# Key_Pass.net
KiCad netlist of a schematic drawn in EAGLE
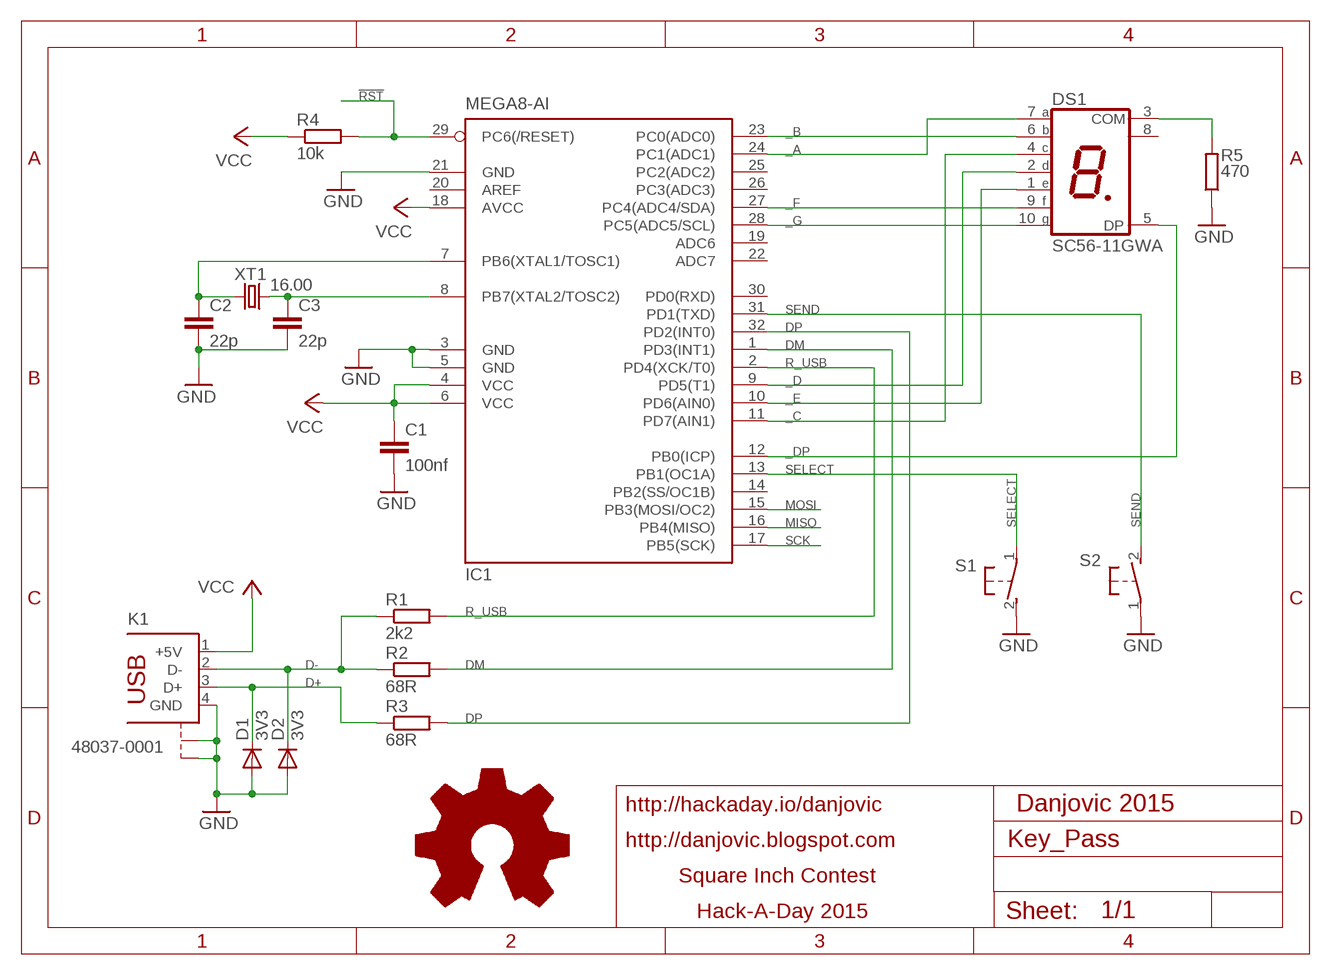
[diagram p0: schematic, sheet 1]

(export (version "E")
  (design (tool "Eeschema 10.0.6"))
  (components
    (comp (ref "C1")
      (value "100nf")
      (footprint "eagle-import:C1206")
      (libsource (lib "eagle-import") (part "C-EUC1206"))
    )
    (comp (ref "C2")
      (value "22p")
      (footprint "eagle-import:C0805")
      (libsource (lib "eagle-import") (part "C-EUC0805"))
    )
    (comp (ref "C3")
      (value "22p")
      (footprint "eagle-import:C0805")
      (libsource (lib "eagle-import") (part "C-EUC0805"))
    )
    (comp (ref "D1")
      (value "3V3")
      (footprint "eagle-import:SOD80C")
      (libsource (lib "eagle-import") (part "DIODE-SOD80C"))
    )
    (comp (ref "D2")
      (value "3V3")
      (footprint "eagle-import:SOD80C")
      (libsource (lib "eagle-import") (part "DIODE-SOD80C"))
    )
    (comp (ref "DS1")
      (value "SC56-11GWA")
      (footprint "eagle-import:SA52-11")
      (libsource (lib "eagle-import") (part "7-SEG_SA52-11"))
    )
    (comp (ref "IC1")
      (value "MEGA8-AI")
      (footprint "eagle-import:TQFP32-08")
      (fields (field (name "MPN") "ATMEGA8-16AU"))
      (libsource (lib "eagle-import") (part "MEGA8-AI"))
    )
    (comp (ref "K1")
      (value "48037-0001")
      (footprint "eagle-import:48037-0001")
      (libsource (lib "eagle-import") (part "48037-0001"))
    )
    (comp (ref "R1")
      (value "2k2")
      (footprint "eagle-import:R0805")
      (libsource (lib "eagle-import") (part "R-EU_R0805"))
    )
    (comp (ref "R2")
      (value "68R")
      (footprint "eagle-import:R0805")
      (libsource (lib "eagle-import") (part "R-EU_R0805"))
    )
    (comp (ref "R3")
      (value "68R")
      (footprint "eagle-import:R0805")
      (libsource (lib "eagle-import") (part "R-EU_R0805"))
    )
    (comp (ref "R4")
      (value "10k")
      (footprint "eagle-import:R0805")
      (libsource (lib "eagle-import") (part "R-EU_R0805"))
    )
    (comp (ref "R5")
      (value "470")
      (footprint "eagle-import:R0805")
      (libsource (lib "eagle-import") (part "R-EU_R0805"))
    )
    (comp (ref "S1")
      (value "31-XX")
      (footprint "eagle-import:B3F-31XX")
      (fields (field (name "MPN") "B3F-3100"))
      (libsource (lib "eagle-import") (part "31-XX"))
    )
    (comp (ref "S2")
      (value "31-XX")
      (footprint "eagle-import:B3F-31XX")
      (fields (field (name "MPN") "B3F-3100"))
      (libsource (lib "eagle-import") (part "31-XX"))
    )
    (comp (ref "XT1")
      (value "16.00")
      (footprint "eagle-import:HC49UP")
      (libsource (lib "eagle-import") (part "CRYSTALHC49UP"))
    )
  )
  (nets
    (net (code "1") (name "/D+") (class "Default")
      (node (ref "D1") (pin "C") (pinfunction "C_C") (pintype "passive"))
      (node (ref "K1") (pin "3") (pinfunction "D+_3") (pintype "passive"))
      (node (ref "R3") (pin "1") (pinfunction "1_1") (pintype "passive"))
    )
    (net (code "2") (name "/D-") (class "Default")
      (node (ref "D2") (pin "C") (pinfunction "C_C") (pintype "passive"))
      (node (ref "K1") (pin "2") (pinfunction "D-_2") (pintype "passive"))
      (node (ref "R1") (pin "1") (pinfunction "1_1") (pintype "passive"))
      (node (ref "R2") (pin "1") (pinfunction "1_1") (pintype "passive"))
    )
    (net (code "3") (name "/DM") (class "Default")
      (node (ref "IC1") (pin "1") (pinfunction "PD3(INT1)_1") (pintype "bidirectional"))
      (node (ref "R2") (pin "2") (pinfunction "2_2") (pintype "passive"))
    )
    (net (code "4") (name "/DP") (class "Default")
      (node (ref "IC1") (pin "32") (pinfunction "PD2(INT0)_32") (pintype "bidirectional"))
      (node (ref "R3") (pin "2") (pinfunction "2_2") (pintype "passive"))
    )
    (net (code "5") (name "/MISO") (class "Default")
      (node (ref "IC1") (pin "16") (pinfunction "PB4(MISO)_16") (pintype "bidirectional"))
    )
    (net (code "6") (name "/MOSI") (class "Default")
      (node (ref "IC1") (pin "15") (pinfunction "PB3(MOSI/OC2)_15") (pintype "bidirectional"))
    )
    (net (code "7") (name "/R_USB") (class "Default")
      (node (ref "IC1") (pin "2") (pinfunction "PD4(XCK/T0)_2") (pintype "bidirectional"))
      (node (ref "R1") (pin "2") (pinfunction "2_2") (pintype "passive"))
    )
    (net (code "8") (name "/SCK") (class "Default")
      (node (ref "IC1") (pin "17") (pinfunction "PB5(SCK)_17") (pintype "bidirectional"))
    )
    (net (code "9") (name "/SELECT") (class "Default")
      (node (ref "IC1") (pin "13") (pinfunction "PB1(OC1A)_13") (pintype "bidirectional"))
      (node (ref "S1") (pin "1") (pinfunction "P_1") (pintype "passive"))
    )
    (net (code "10") (name "/SEND") (class "Default")
      (node (ref "IC1") (pin "31") (pinfunction "PD1(TXD)_31") (pintype "bidirectional"))
      (node (ref "S2") (pin "2") (pinfunction "S_2") (pintype "passive"))
    )
    (net (code "11") (name "/_A") (class "Default")
      (node (ref "DS1") (pin "7") (pinfunction "A_7") (pintype "passive"))
      (node (ref "IC1") (pin "24") (pinfunction "PC1(ADC1)_24") (pintype "bidirectional"))
    )
    (net (code "12") (name "/_B") (class "Default")
      (node (ref "DS1") (pin "6") (pinfunction "B_6") (pintype "passive"))
      (node (ref "IC1") (pin "23") (pinfunction "PC0(ADC0)_23") (pintype "bidirectional"))
    )
    (net (code "13") (name "/_C") (class "Default")
      (node (ref "DS1") (pin "4") (pinfunction "C_4") (pintype "passive"))
      (node (ref "IC1") (pin "11") (pinfunction "PD7(AIN1)_11") (pintype "bidirectional"))
    )
    (net (code "14") (name "/_D") (class "Default")
      (node (ref "DS1") (pin "2") (pinfunction "D_2") (pintype "passive"))
      (node (ref "IC1") (pin "9") (pinfunction "PD5(T1)_9") (pintype "bidirectional"))
    )
    (net (code "15") (name "/_DP") (class "Default")
      (node (ref "DS1") (pin "5") (pinfunction "DP_5") (pintype "passive"))
      (node (ref "IC1") (pin "12") (pinfunction "PB0(ICP)_12") (pintype "bidirectional"))
    )
    (net (code "16") (name "/_E") (class "Default")
      (node (ref "DS1") (pin "1") (pinfunction "E_1") (pintype "passive"))
      (node (ref "IC1") (pin "10") (pinfunction "PD6(AIN0)_10") (pintype "bidirectional"))
    )
    (net (code "17") (name "/_F") (class "Default")
      (node (ref "DS1") (pin "9") (pinfunction "F_9") (pintype "passive"))
      (node (ref "IC1") (pin "27") (pinfunction "PC4(ADC4/SDA)_27") (pintype "bidirectional"))
    )
    (net (code "18") (name "/_G") (class "Default")
      (node (ref "DS1") (pin "10") (pinfunction "G_10") (pintype "passive"))
      (node (ref "IC1") (pin "28") (pinfunction "PC5(ADC5/SCL)_28") (pintype "bidirectional"))
    )
    (net (code "19") (name "/~{RST}") (class "Default")
      (node (ref "IC1") (pin "29") (pinfunction "PC6(/RESET)_29") (pintype "bidirectional"))
      (node (ref "R4") (pin "2") (pinfunction "2_2") (pintype "passive"))
    )
    (net (code "20") (name "GND") (class "Default")
      (node (ref "C1") (pin "2") (pinfunction "2_2") (pintype "passive"))
      (node (ref "C2") (pin "1") (pinfunction "1_1") (pintype "passive"))
      (node (ref "C3") (pin "1") (pinfunction "1_1") (pintype "passive"))
      (node (ref "D1") (pin "A") (pinfunction "A_A") (pintype "passive"))
      (node (ref "D2") (pin "A") (pinfunction "A_A") (pintype "passive"))
      (node (ref "IC1") (pin "21") (pinfunction "GND_21") (pintype "power_in"))
      (node (ref "IC1") (pin "3") (pinfunction "GND_3") (pintype "power_in"))
      (node (ref "IC1") (pin "5") (pinfunction "GND_5") (pintype "power_in"))
      (node (ref "K1") (pin "4") (pinfunction "GND_4") (pintype "passive"))
      (node (ref "K1") (pin "P$1") (pinfunction "S1_P$1") (pintype "passive"))
      (node (ref "K1") (pin "P$2") (pinfunction "S2_P$2") (pintype "passive"))
      (node (ref "R5") (pin "1") (pinfunction "1_1") (pintype "passive"))
      (node (ref "S1") (pin "2") (pinfunction "S_2") (pintype "passive"))
      (node (ref "S2") (pin "1") (pinfunction "P_1") (pintype "passive"))
    )
    (net (code "21") (name "Net-(DS1-COM-Pad3)") (class "Default")
      (node (ref "DS1") (pin "3") (pinfunction "COM_3") (pintype "passive"))
      (node (ref "R5") (pin "2") (pinfunction "2_2") (pintype "passive"))
    )
    (net (code "22") (name "Net-(IC1-PB6(XTAL1{slash}TOSC1))") (class "Default")
      (node (ref "C2") (pin "2") (pinfunction "2_2") (pintype "passive"))
      (node (ref "IC1") (pin "7") (pinfunction "PB6(XTAL1/TOSC1)_7") (pintype "bidirectional"))
      (node (ref "XT1") (pin "1") (pinfunction "1_1") (pintype "passive"))
    )
    (net (code "23") (name "Net-(IC1-PB7(XTAL2{slash}TOSC2))") (class "Default")
      (node (ref "C3") (pin "2") (pinfunction "2_2") (pintype "passive"))
      (node (ref "IC1") (pin "8") (pinfunction "PB7(XTAL2/TOSC2)_8") (pintype "bidirectional"))
      (node (ref "XT1") (pin "2") (pinfunction "2_2") (pintype "passive"))
    )
    (net (code "24") (name "VCC") (class "Default")
      (node (ref "C1") (pin "1") (pinfunction "1_1") (pintype "passive"))
      (node (ref "IC1") (pin "18") (pinfunction "AVCC_18") (pintype "power_in"))
      (node (ref "IC1") (pin "4") (pinfunction "VCC_4") (pintype "power_in"))
      (node (ref "IC1") (pin "6") (pinfunction "VCC_6") (pintype "power_in"))
      (node (ref "K1") (pin "1") (pinfunction "+5V_1") (pintype "passive"))
      (node (ref "R4") (pin "1") (pinfunction "1_1") (pintype "passive"))
    )
    (net (code "25") (name "unconnected-(DS1-COM-Pad8)") (class "Default")
      (node (ref "DS1") (pin "8") (pinfunction "COM_8") (pintype "passive"))
    )
    (net (code "26") (name "unconnected-(IC1-ADC6-Pad19)") (class "Default")
      (node (ref "IC1") (pin "19") (pinfunction "ADC6_19") (pintype "bidirectional"))
    )
    (net (code "27") (name "unconnected-(IC1-ADC7-Pad22)") (class "Default")
      (node (ref "IC1") (pin "22") (pinfunction "ADC7_22") (pintype "bidirectional"))
    )
    (net (code "28") (name "unconnected-(IC1-AREF-Pad20)") (class "Default")
      (node (ref "IC1") (pin "20") (pinfunction "AREF_20") (pintype "passive"))
    )
    (net (code "29") (name "unconnected-(IC1-PB2(SS{slash}OC1B)-Pad14)") (class "Default")
      (node (ref "IC1") (pin "14") (pinfunction "PB2(SS/OC1B)_14") (pintype "bidirectional"))
    )
    (net (code "30") (name "unconnected-(IC1-PC2(ADC2)-Pad25)") (class "Default")
      (node (ref "IC1") (pin "25") (pinfunction "PC2(ADC2)_25") (pintype "bidirectional"))
    )
    (net (code "31") (name "unconnected-(IC1-PC3(ADC3)-Pad26)") (class "Default")
      (node (ref "IC1") (pin "26") (pinfunction "PC3(ADC3)_26") (pintype "bidirectional"))
    )
    (net (code "32") (name "unconnected-(IC1-PD0(RXD)-Pad30)") (class "Default")
      (node (ref "IC1") (pin "30") (pinfunction "PD0(RXD)_30") (pintype "bidirectional"))
    )
  )
)
